# encoder_adapter.net
KiCad netlist of a schematic drawn in EAGLE
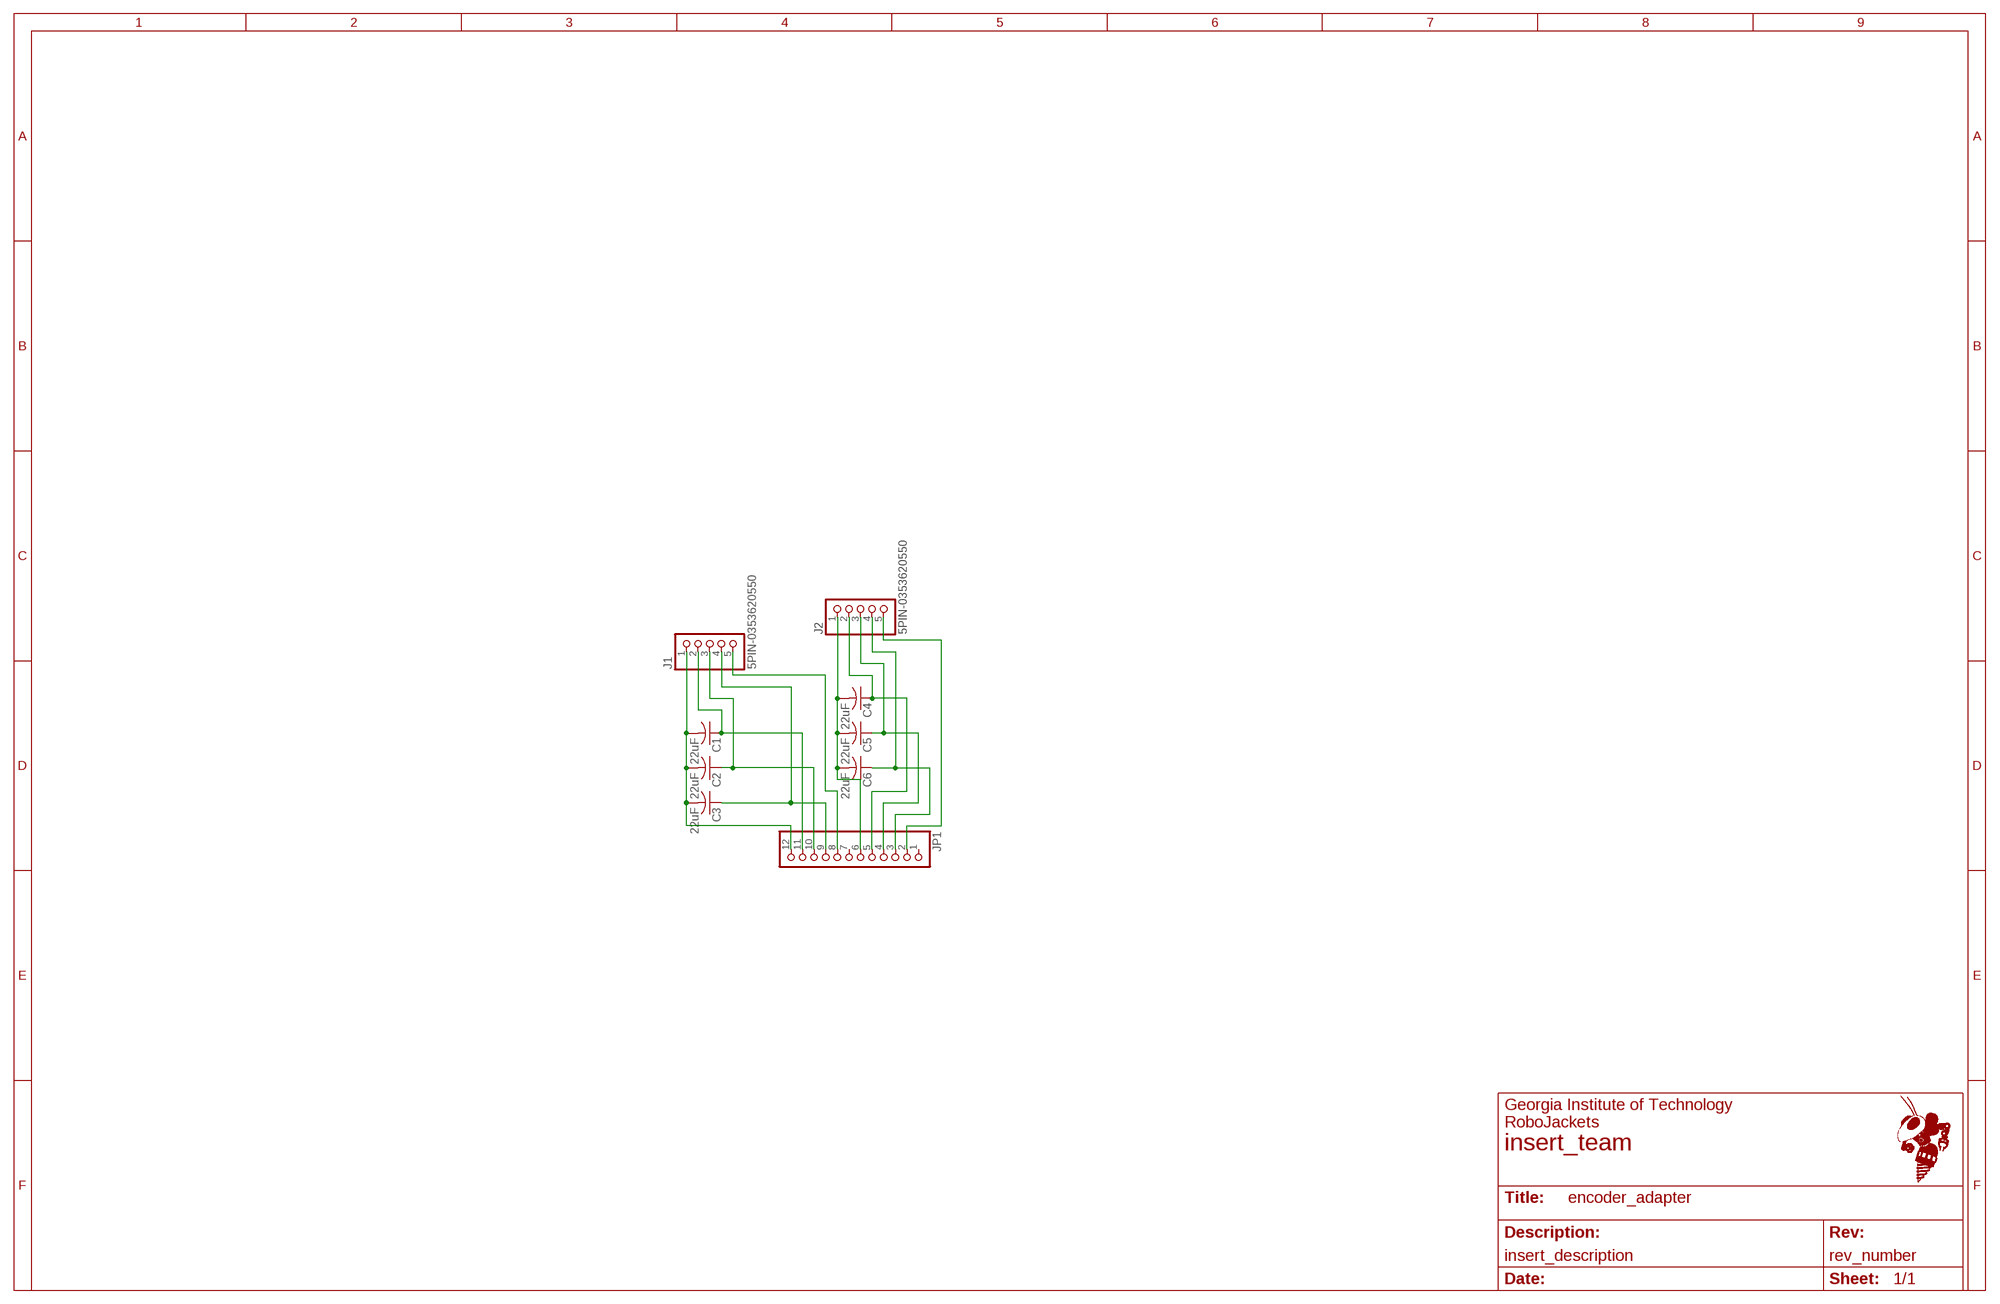
[diagram p0: schematic, sheet 1]

(export (version "E")
  (design (tool "Eeschema 10.0.6"))
  (components
    (comp (ref "C1")
      (value "22uF")
      (footprint "eagle-import:C0805")
      (libsource (lib "eagle-import") (part "C-USC0805"))
    )
    (comp (ref "C2")
      (value "22uF")
      (footprint "eagle-import:C0805")
      (libsource (lib "eagle-import") (part "C-USC0805"))
    )
    (comp (ref "C3")
      (value "22uF")
      (footprint "eagle-import:C0805")
      (libsource (lib "eagle-import") (part "C-USC0805"))
    )
    (comp (ref "C4")
      (value "22uF")
      (footprint "eagle-import:C0805")
      (libsource (lib "eagle-import") (part "C-USC0805"))
    )
    (comp (ref "C5")
      (value "22uF")
      (footprint "eagle-import:C0805")
      (libsource (lib "eagle-import") (part "C-USC0805"))
    )
    (comp (ref "C6")
      (value "22uF")
      (footprint "eagle-import:C0805")
      (libsource (lib "eagle-import") (part "C-USC0805"))
    )
    (comp (ref "J1")
      (value "5PIN-0353620550")
      (footprint "eagle-import:0353620550")
      (libsource (lib "eagle-import") (part "5PIN-03536?20550"))
    )
    (comp (ref "J2")
      (value "5PIN-0353620550")
      (footprint "eagle-import:0353620550")
      (libsource (lib "eagle-import") (part "5PIN-03536?20550"))
    )
    (comp (ref "JP1")
      (value "PINHD-1X12")
      (footprint "eagle-import:1X12")
      (libsource (lib "eagle-import") (part "PINHD-1X12"))
    )
  )
  (nets
    (net (code "1") (name "Net-(C1-Pad1)") (class "Default")
      (node (ref "C1") (pin "1") (pinfunction "1_1") (pintype "passive"))
      (node (ref "J1") (pin "2") (pinfunction "2_2") (pintype "passive"))
      (node (ref "JP1") (pin "11") (pinfunction "11_11") (pintype "passive"))
    )
    (net (code "2") (name "Net-(C1-Pad2)") (class "Default")
      (node (ref "C1") (pin "2") (pinfunction "2_2") (pintype "passive"))
      (node (ref "C2") (pin "2") (pinfunction "2_2") (pintype "passive"))
      (node (ref "C3") (pin "2") (pinfunction "2_2") (pintype "passive"))
      (node (ref "J1") (pin "1") (pinfunction "1_1") (pintype "passive"))
      (node (ref "JP1") (pin "12") (pinfunction "12_12") (pintype "passive"))
    )
    (net (code "3") (name "Net-(C2-Pad1)") (class "Default")
      (node (ref "C2") (pin "1") (pinfunction "1_1") (pintype "passive"))
      (node (ref "J1") (pin "3") (pinfunction "3_3") (pintype "passive"))
      (node (ref "JP1") (pin "10") (pinfunction "10_10") (pintype "passive"))
    )
    (net (code "4") (name "Net-(C3-Pad1)") (class "Default")
      (node (ref "C3") (pin "1") (pinfunction "1_1") (pintype "passive"))
      (node (ref "J1") (pin "4") (pinfunction "4_4") (pintype "passive"))
      (node (ref "JP1") (pin "9") (pinfunction "9_9") (pintype "passive"))
    )
    (net (code "5") (name "Net-(C4-Pad1)") (class "Default")
      (node (ref "C4") (pin "1") (pinfunction "1_1") (pintype "passive"))
      (node (ref "J2") (pin "2") (pinfunction "2_2") (pintype "passive"))
      (node (ref "JP1") (pin "5") (pinfunction "5_5") (pintype "passive"))
    )
    (net (code "6") (name "Net-(C4-Pad2)") (class "Default")
      (node (ref "C4") (pin "2") (pinfunction "2_2") (pintype "passive"))
      (node (ref "C5") (pin "2") (pinfunction "2_2") (pintype "passive"))
      (node (ref "C6") (pin "2") (pinfunction "2_2") (pintype "passive"))
      (node (ref "J2") (pin "1") (pinfunction "1_1") (pintype "passive"))
      (node (ref "JP1") (pin "6") (pinfunction "6_6") (pintype "passive"))
    )
    (net (code "7") (name "Net-(C5-Pad1)") (class "Default")
      (node (ref "C5") (pin "1") (pinfunction "1_1") (pintype "passive"))
      (node (ref "J2") (pin "3") (pinfunction "3_3") (pintype "passive"))
      (node (ref "JP1") (pin "4") (pinfunction "4_4") (pintype "passive"))
    )
    (net (code "8") (name "Net-(C6-Pad1)") (class "Default")
      (node (ref "C6") (pin "1") (pinfunction "1_1") (pintype "passive"))
      (node (ref "J2") (pin "4") (pinfunction "4_4") (pintype "passive"))
      (node (ref "JP1") (pin "3") (pinfunction "3_3") (pintype "passive"))
    )
    (net (code "9") (name "Net-(J1-Pad5)") (class "Default")
      (node (ref "J1") (pin "5") (pinfunction "5_5") (pintype "passive"))
      (node (ref "JP1") (pin "8") (pinfunction "8_8") (pintype "passive"))
    )
    (net (code "10") (name "Net-(J2-Pad5)") (class "Default")
      (node (ref "J2") (pin "5") (pinfunction "5_5") (pintype "passive"))
      (node (ref "JP1") (pin "2") (pinfunction "2_2") (pintype "passive"))
    )
    (net (code "11") (name "unconnected-(JP1-Pad1)") (class "Default")
      (node (ref "JP1") (pin "1") (pinfunction "1_1") (pintype "passive"))
    )
    (net (code "12") (name "unconnected-(JP1-Pad7)") (class "Default")
      (node (ref "JP1") (pin "7") (pinfunction "7_7") (pintype "passive"))
    )
  )
)
